# usbUnifier.net
KiCad netlist of a schematic drawn in EAGLE
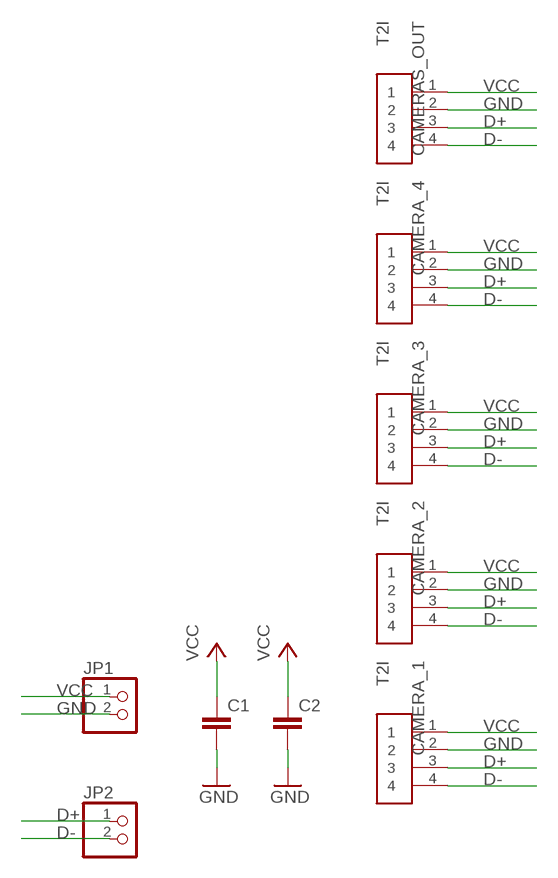
[diagram p0: schematic, sheet 1]

(export (version "E")
  (design (tool "Eeschema 10.0.6"))
  (components
    (comp (ref "C1")
      (value "C-EUC0603")
      (footprint "eagle-import:C0603")
      (libsource (lib "eagle-import") (part "C-EUC0603"))
    )
    (comp (ref "C2")
      (value "C-EUC0603")
      (footprint "eagle-import:C0603")
      (libsource (lib "eagle-import") (part "C-EUC0603"))
    )
    (comp (ref "CAMERAS_OUT")
      (value "T2I")
      (footprint "eagle-import:T2I")
      (libsource (lib "eagle-import") (part "T2I"))
    )
    (comp (ref "CAMERA_1")
      (value "T2I")
      (footprint "eagle-import:T2I")
      (libsource (lib "eagle-import") (part "T2I"))
    )
    (comp (ref "CAMERA_2")
      (value "T2I")
      (footprint "eagle-import:T2I")
      (libsource (lib "eagle-import") (part "T2I"))
    )
    (comp (ref "CAMERA_3")
      (value "T2I")
      (footprint "eagle-import:T2I")
      (libsource (lib "eagle-import") (part "T2I"))
    )
    (comp (ref "CAMERA_4")
      (value "T2I")
      (footprint "eagle-import:T2I")
      (libsource (lib "eagle-import") (part "T2I"))
    )
    (comp (ref "JP1")
      (value "PINHD-1X2")
      (footprint "eagle-import:1X02")
      (libsource (lib "eagle-import") (part "PINHD-1X2"))
    )
    (comp (ref "JP2")
      (value "PINHD-1X2")
      (footprint "eagle-import:1X02")
      (libsource (lib "eagle-import") (part "PINHD-1X2"))
    )
  )
  (nets
    (net (code "1") (name "/D+") (class "Default")
      (node (ref "CAMERAS_OUT") (pin "3") (pinfunction "3_3") (pintype "bidirectional"))
      (node (ref "CAMERA_1") (pin "3") (pinfunction "3_3") (pintype "bidirectional"))
      (node (ref "CAMERA_2") (pin "3") (pinfunction "3_3") (pintype "bidirectional"))
      (node (ref "CAMERA_3") (pin "3") (pinfunction "3_3") (pintype "bidirectional"))
      (node (ref "CAMERA_4") (pin "3") (pinfunction "3_3") (pintype "bidirectional"))
      (node (ref "JP2") (pin "1") (pinfunction "1_1") (pintype "passive"))
    )
    (net (code "2") (name "/D-") (class "Default")
      (node (ref "CAMERAS_OUT") (pin "4") (pinfunction "4_4") (pintype "bidirectional"))
      (node (ref "CAMERA_1") (pin "4") (pinfunction "4_4") (pintype "bidirectional"))
      (node (ref "CAMERA_2") (pin "4") (pinfunction "4_4") (pintype "bidirectional"))
      (node (ref "CAMERA_3") (pin "4") (pinfunction "4_4") (pintype "bidirectional"))
      (node (ref "CAMERA_4") (pin "4") (pinfunction "4_4") (pintype "bidirectional"))
      (node (ref "JP2") (pin "2") (pinfunction "2_2") (pintype "passive"))
    )
    (net (code "3") (name "GND") (class "Default")
      (node (ref "C1") (pin "2") (pinfunction "2_2") (pintype "passive"))
      (node (ref "C2") (pin "2") (pinfunction "2_2") (pintype "passive"))
      (node (ref "CAMERAS_OUT") (pin "2") (pinfunction "2_2") (pintype "bidirectional"))
      (node (ref "CAMERA_1") (pin "2") (pinfunction "2_2") (pintype "bidirectional"))
      (node (ref "CAMERA_2") (pin "2") (pinfunction "2_2") (pintype "bidirectional"))
      (node (ref "CAMERA_3") (pin "2") (pinfunction "2_2") (pintype "bidirectional"))
      (node (ref "CAMERA_4") (pin "2") (pinfunction "2_2") (pintype "bidirectional"))
      (node (ref "JP1") (pin "2") (pinfunction "2_2") (pintype "passive"))
    )
    (net (code "4") (name "VCC") (class "Default")
      (node (ref "C1") (pin "1") (pinfunction "1_1") (pintype "passive"))
      (node (ref "C2") (pin "1") (pinfunction "1_1") (pintype "passive"))
      (node (ref "CAMERAS_OUT") (pin "1") (pinfunction "1_1") (pintype "bidirectional"))
      (node (ref "CAMERA_1") (pin "1") (pinfunction "1_1") (pintype "bidirectional"))
      (node (ref "CAMERA_2") (pin "1") (pinfunction "1_1") (pintype "bidirectional"))
      (node (ref "CAMERA_3") (pin "1") (pinfunction "1_1") (pintype "bidirectional"))
      (node (ref "CAMERA_4") (pin "1") (pinfunction "1_1") (pintype "bidirectional"))
      (node (ref "JP1") (pin "1") (pinfunction "1_1") (pintype "passive"))
    )
  )
)
